# leo_MCU.net
KiCad netlist of a schematic drawn in Altium Designer
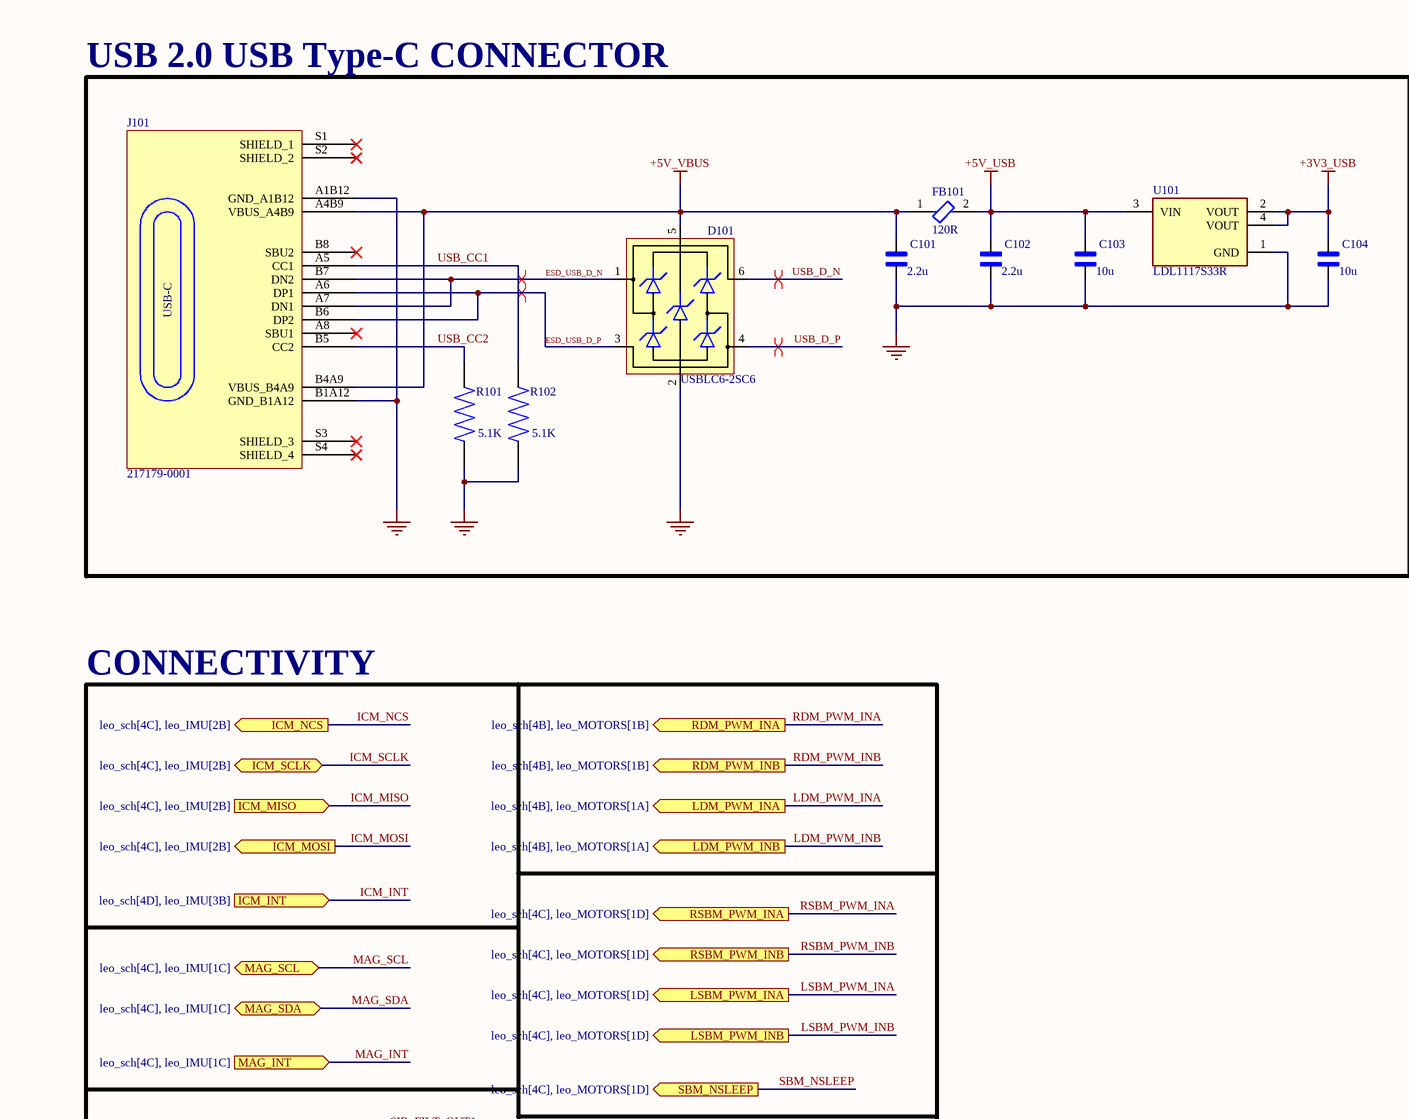
[diagram p0: leo_MCU.SchDoc, top left]
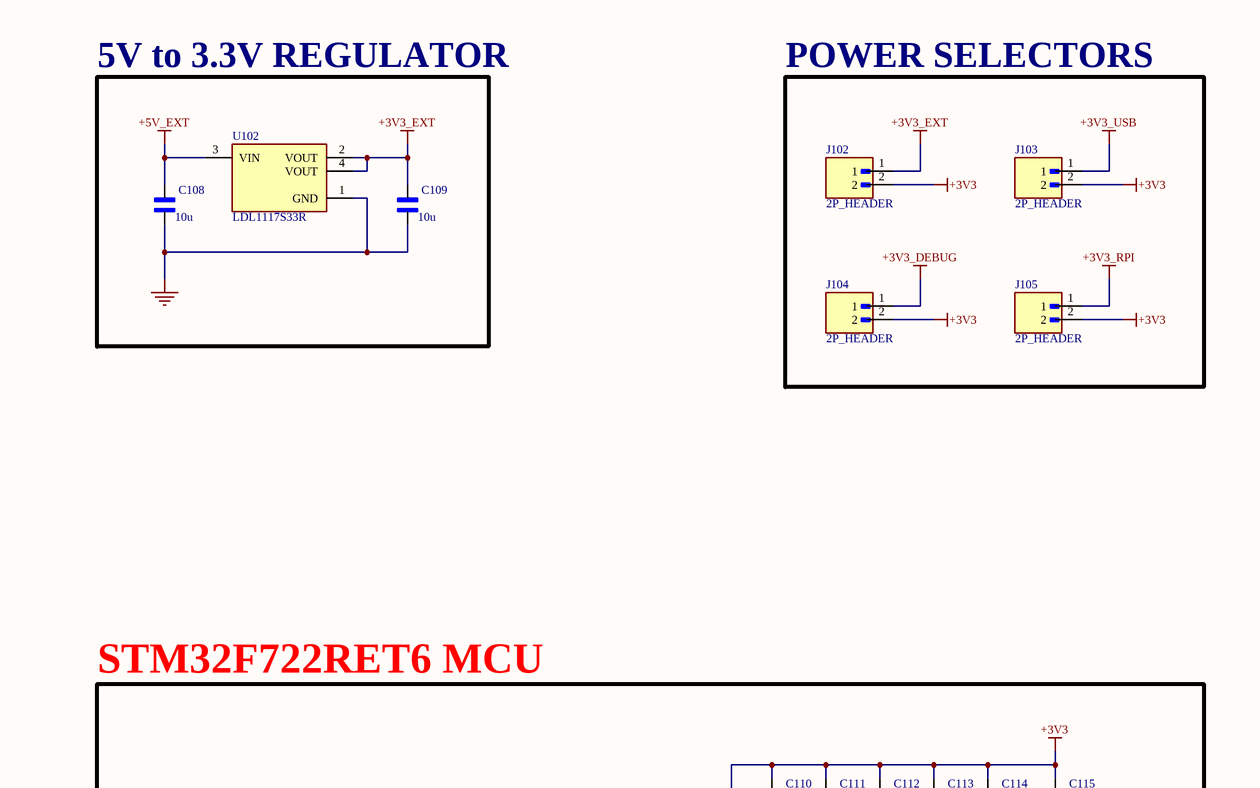
[diagram p1: leo_MCU.SchDoc, top right]
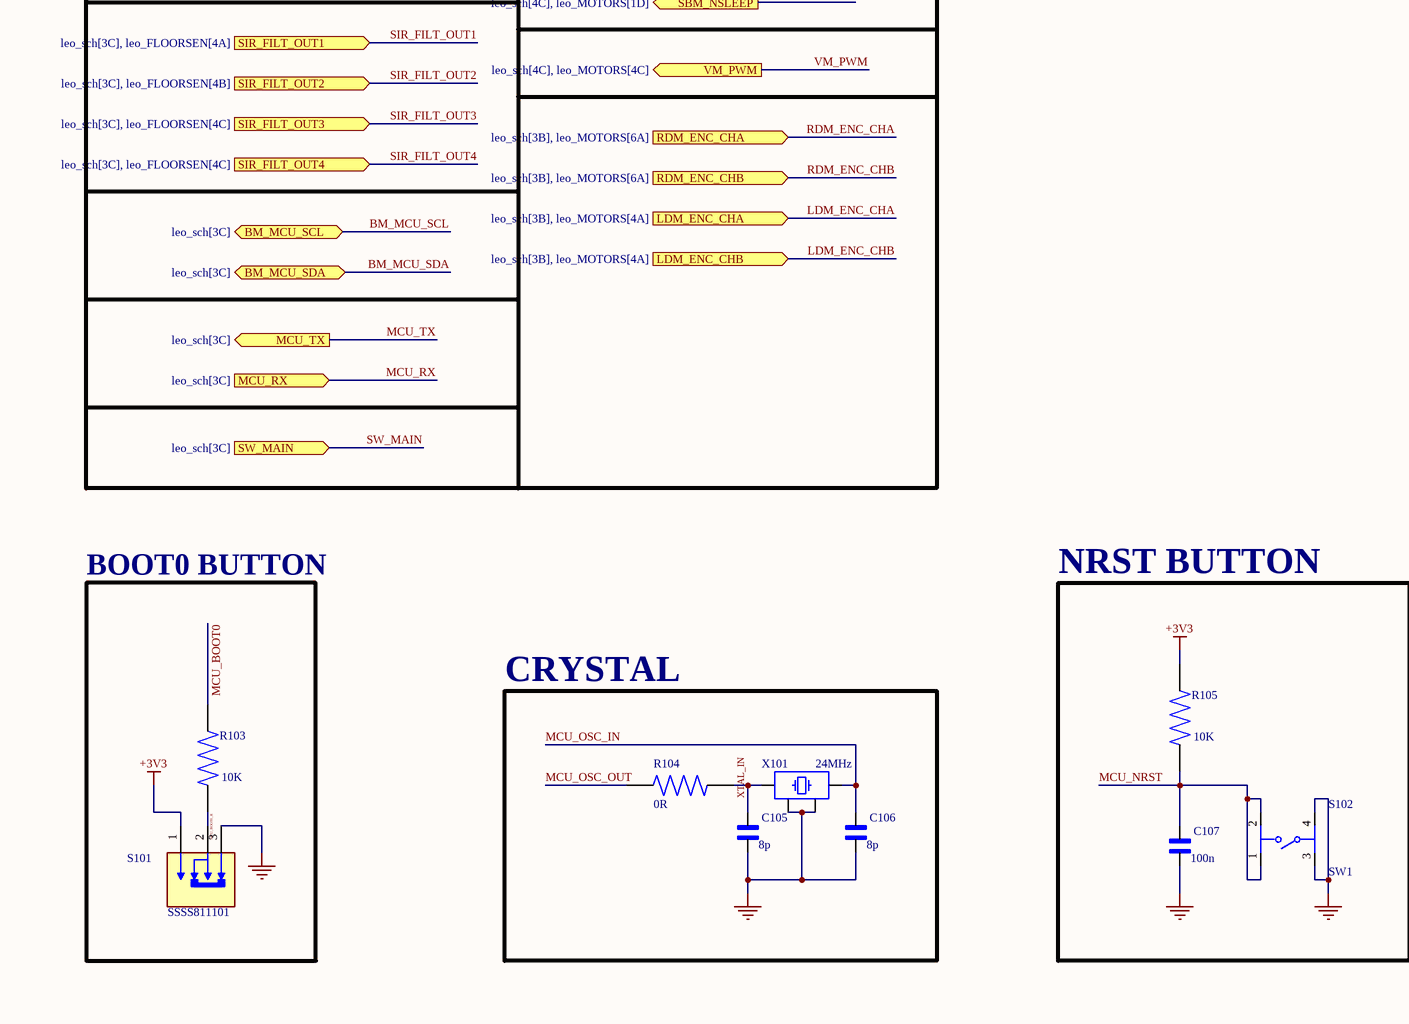
[diagram p2: leo_MCU.SchDoc, bottom left]
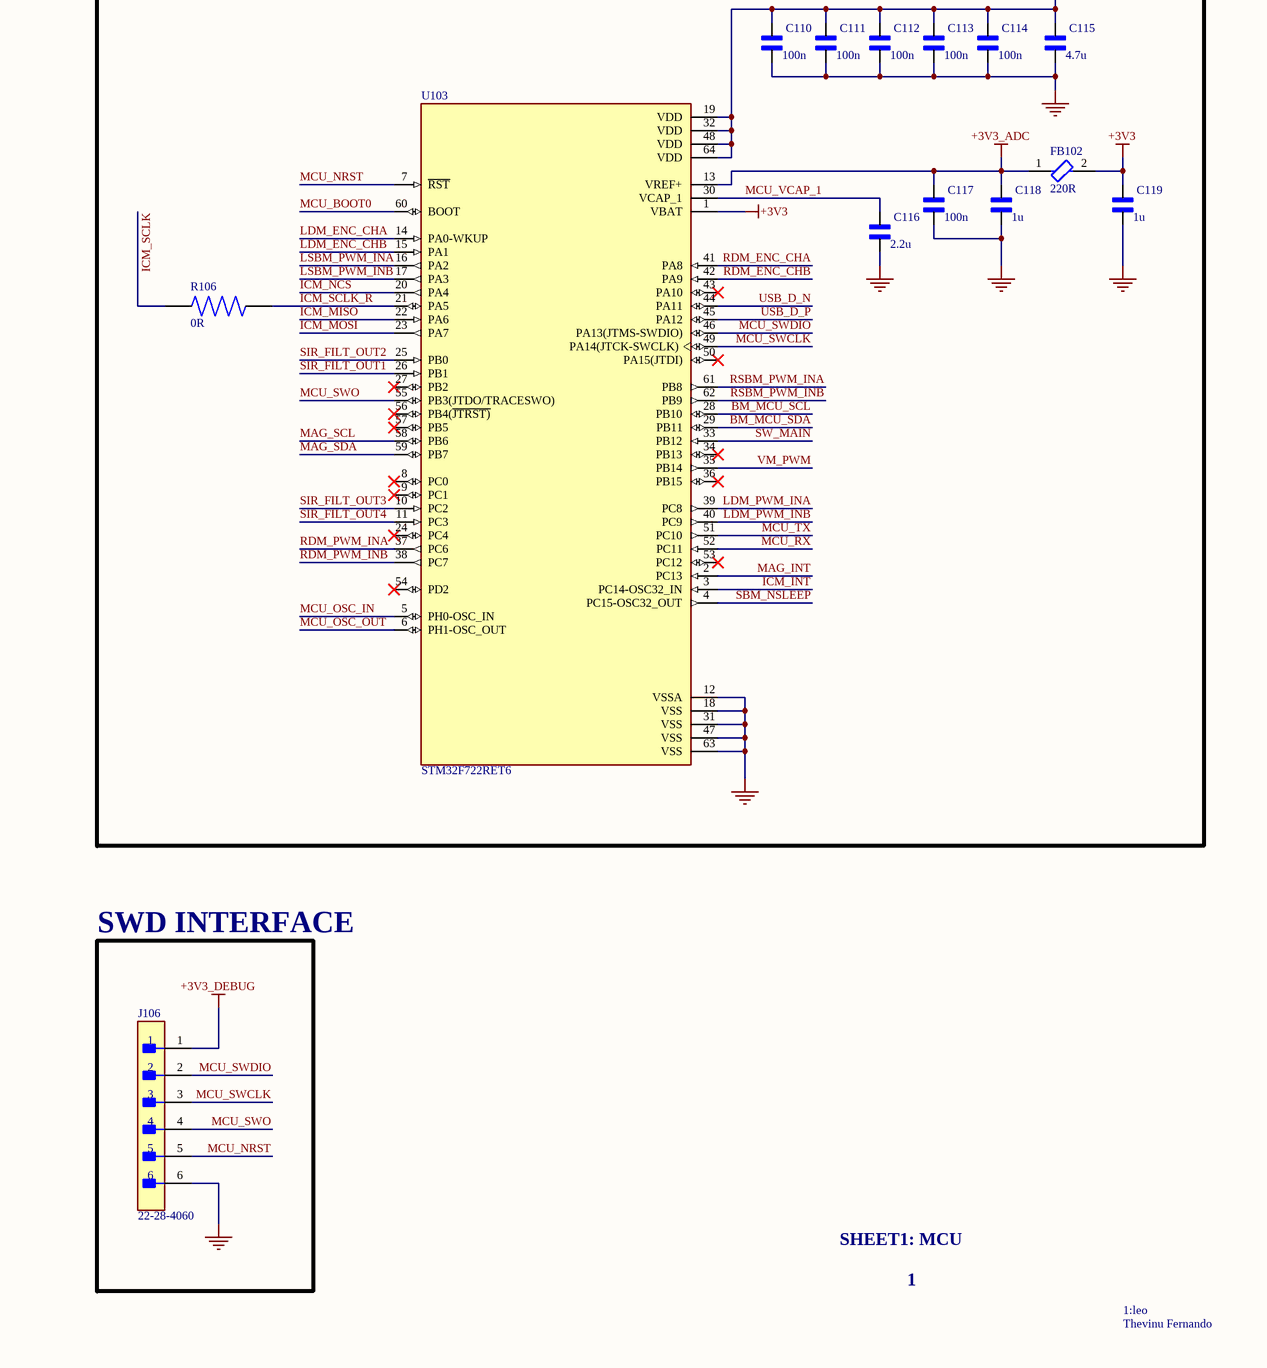
[diagram p3: leo_MCU.SchDoc, bottom right]

(export (version "E")
  (design (tool "Eeschema 10.0.6"))
  (components
    (comp (ref "C101")
      (value "2.2u")
      (footprint "CAP_0603")
      (description "Ceramic Capacitor X5R 0603 (1608 Metric)")
      (fields (field (name "MF") "Samsung Electro-Mechanics") (field (name "MP") "CL10A475KO8NNNC"))
      (libsource (lib "leo_schlib") (part "CAP_0603"))
    )
    (comp (ref "C102")
      (value "2.2u")
      (footprint "CAP_0603")
      (description "Ceramic Capacitor X5R 0603 (1608 Metric)")
      (fields (field (name "MF") "Samsung Electro-Mechanics") (field (name "MP") "CL10A475KO8NNNC"))
      (libsource (lib "leo_schlib") (part "CAP_0603"))
    )
    (comp (ref "C103")
      (value "10u")
      (footprint "CAP_0805")
      (description "Ceramic Capacitor X7R 0805 (2012 Metric)")
      (fields (field (name "MF") "Samsung Electro-Mechanics") (field (name "MP") "CL21B106KOQNNNE"))
      (libsource (lib "leo_schlib") (part "CAP_0805"))
    )
    (comp (ref "C104")
      (value "10u")
      (footprint "CAP_0805")
      (description "Ceramic Capacitor X7R 0805 (2012 Metric)")
      (fields (field (name "MF") "Samsung Electro-Mechanics") (field (name "MP") "CL21B106KOQNNNE"))
      (libsource (lib "leo_schlib") (part "CAP_0805"))
    )
    (comp (ref "C105")
      (value "8p")
      (footprint "CAP_0402")
      (description "Ceramic Capacitor X7R 0402 (1005 Metric)")
      (fields (field (name "MF") "Samsung") (field (name "MP") "CL05B104KO5NNNC"))
      (libsource (lib "leo_schlib") (part "CAP_0402"))
    )
    (comp (ref "C106")
      (value "8p")
      (footprint "CAP_0402")
      (description "Ceramic Capacitor X7R 0402 (1005 Metric)")
      (fields (field (name "MF") "Samsung") (field (name "MP") "CL05B104KO5NNNC"))
      (libsource (lib "leo_schlib") (part "CAP_0402"))
    )
    (comp (ref "C107")
      (value "100n")
      (footprint "CAP_0402")
      (description "Ceramic Capacitor X7R 0402 (1005 Metric)")
      (fields (field (name "MF") "Samsung") (field (name "MP") "CL05B104KO5NNNC"))
      (libsource (lib "leo_schlib") (part "CAP_0402"))
    )
    (comp (ref "C108")
      (value "10u")
      (footprint "CAP_0805")
      (description "Ceramic Capacitor X7R 0805 (2012 Metric)")
      (fields (field (name "MF") "Samsung Electro-Mechanics") (field (name "MP") "CL21B106KOQNNNE"))
      (libsource (lib "leo_schlib") (part "CAP_0805"))
    )
    (comp (ref "C109")
      (value "10u")
      (footprint "CAP_0805")
      (description "Ceramic Capacitor X7R 0805 (2012 Metric)")
      (fields (field (name "MF") "Samsung Electro-Mechanics") (field (name "MP") "CL21B106KOQNNNE"))
      (libsource (lib "leo_schlib") (part "CAP_0805"))
    )
    (comp (ref "C110")
      (value "100n")
      (footprint "CAP_0402")
      (description "Ceramic Capacitor X7R 0402 (1005 Metric)")
      (fields (field (name "MF") "Samsung") (field (name "MP") "CL05B104KO5NNNC"))
      (libsource (lib "leo_schlib") (part "CAP_0402"))
    )
    (comp (ref "C111")
      (value "100n")
      (footprint "CAP_0402")
      (description "Ceramic Capacitor X7R 0402 (1005 Metric)")
      (fields (field (name "MF") "Samsung") (field (name "MP") "CL05B104KO5NNNC"))
      (libsource (lib "leo_schlib") (part "CAP_0402"))
    )
    (comp (ref "C112")
      (value "100n")
      (footprint "CAP_0402")
      (description "Ceramic Capacitor X7R 0402 (1005 Metric)")
      (fields (field (name "MF") "Samsung") (field (name "MP") "CL05B104KO5NNNC"))
      (libsource (lib "leo_schlib") (part "CAP_0402"))
    )
    (comp (ref "C113")
      (value "100n")
      (footprint "CAP_0402")
      (description "Ceramic Capacitor X7R 0402 (1005 Metric)")
      (fields (field (name "MF") "Samsung") (field (name "MP") "CL05B104KO5NNNC"))
      (libsource (lib "leo_schlib") (part "CAP_0402"))
    )
    (comp (ref "C114")
      (value "100n")
      (footprint "CAP_0402")
      (description "Ceramic Capacitor X7R 0402 (1005 Metric)")
      (fields (field (name "MF") "Samsung") (field (name "MP") "CL05B104KO5NNNC"))
      (libsource (lib "leo_schlib") (part "CAP_0402"))
    )
    (comp (ref "C115")
      (value "4.7u")
      (footprint "CAP_0603")
      (description "Ceramic Capacitor X5R 0603 (1608 Metric)")
      (fields (field (name "MF") "Samsung Electro-Mechanics") (field (name "MP") "CL10A475KO8NNNC"))
      (libsource (lib "leo_schlib") (part "CAP_0603"))
    )
    (comp (ref "C116")
      (value "2.2u")
      (footprint "CAP_0603")
      (description "Ceramic Capacitor X5R 0603 (1608 Metric)")
      (fields (field (name "MF") "Samsung Electro-Mechanics") (field (name "MP") "CL10A475KO8NNNC"))
      (libsource (lib "leo_schlib") (part "CAP_0603"))
    )
    (comp (ref "C117")
      (value "100n")
      (footprint "CAP_0402")
      (description "Ceramic Capacitor X7R 0402 (1005 Metric)")
      (fields (field (name "MF") "Samsung") (field (name "MP") "CL05B104KO5NNNC"))
      (libsource (lib "leo_schlib") (part "CAP_0402"))
    )
    (comp (ref "C118")
      (value "1u")
      (footprint "CAP_0603")
      (description "Ceramic Capacitor X5R 0603 (1608 Metric)")
      (fields (field (name "MF") "Samsung Electro-Mechanics") (field (name "MP") "CL10A475KO8NNNC"))
      (libsource (lib "leo_schlib") (part "CAP_0603"))
    )
    (comp (ref "C119")
      (value "1u")
      (footprint "CAP_0603")
      (description "Ceramic Capacitor X5R 0603 (1608 Metric)")
      (fields (field (name "MF") "Samsung Electro-Mechanics") (field (name "MP") "CL10A475KO8NNNC"))
      (libsource (lib "leo_schlib") (part "CAP_0603"))
    )
    (comp (ref "D101")
      (value "USBLC6-2SC6")
      (footprint "SOT95P280X145-6N")
      (description "Low-Capacitance ESD Protection USB")
      (fields (field (name "MANUFACTURER") "STMicroelectronics"))
      (libsource (lib "leo_schlib") (part "USBLC6-2SC6"))
    )
    (comp (ref "FB101")
      (value "120R")
      (footprint "FP-MPZ1608-0_8-IPC_B")
      (description "120Ω@100MHz 1 Line Ferrite Bead 0603 3A 30mΩ")
      (fields (field (name "TOLERANCE") "25%"))
      (libsource (lib "leo_schlib") (part "Ferrite_Bead_120R_0603"))
    )
    (comp (ref "FB102")
      (value "220R")
      (footprint "FP-MPZ1608-0_8-IPC_B")
      (description "Power line Ferrite Bead 220Ω @ 100MHz 2.2A DCR 0.05Ω SMD 0603")
      (fields (field (name "TOLERANCE") "25%"))
      (libsource (lib "leo_schlib") (part "Ferrite_Bead_0603"))
    )
    (comp (ref "J101")
      (value "217179-0001")
      (footprint "FP-2171790001-MFG USB-C 2.0")
      (description "USB 2.0 5A 1 16P -40℃~+85℃ SMD USB, DVI, HDMI Connector Assemblies RoHS")
      (fields (field (name "MANUFACTURER") "Molex") (field (name "LCSC PART NUMBER") "C3197684"))
      (libsource (lib "leo_schlib") (part "USB_Connector"))
    )
    (comp (ref "J102")
      (value "2P_HEADER")
      (footprint "HARWIN_M20-9990246 2P Header")
      (description "2.54mm (0.1) Pitch SIL Vertical Throughboard Pin Header, 6.1mm mating pin height, tin, 2 contacts")
      (fields (field (name "MF") "Harwin") (field (name "MP") "M20-9990246"))
      (libsource (lib "leo_schlib") (part "2P_HEADER"))
    )
    (comp (ref "J103")
      (value "2P_HEADER")
      (footprint "HARWIN_M20-9990246 2P Header")
      (description "2.54mm (0.1) Pitch SIL Vertical Throughboard Pin Header, 6.1mm mating pin height, tin, 2 contacts")
      (fields (field (name "MF") "Harwin") (field (name "MP") "M20-9990246"))
      (libsource (lib "leo_schlib") (part "2P_HEADER"))
    )
    (comp (ref "J104")
      (value "2P_HEADER")
      (footprint "HARWIN_M20-9990246 2P Header")
      (description "2.54mm (0.1) Pitch SIL Vertical Throughboard Pin Header, 6.1mm mating pin height, tin, 2 contacts")
      (fields (field (name "MF") "Harwin") (field (name "MP") "M20-9990246"))
      (libsource (lib "leo_schlib") (part "2P_HEADER"))
    )
    (comp (ref "J105")
      (value "2P_HEADER")
      (footprint "HARWIN_M20-9990246 2P Header")
      (description "2.54mm (0.1) Pitch SIL Vertical Throughboard Pin Header, 6.1mm mating pin height, tin, 2 contacts")
      (fields (field (name "MF") "Harwin") (field (name "MP") "M20-9990246"))
      (libsource (lib "leo_schlib") (part "2P_HEADER"))
    )
    (comp (ref "J106")
      (value "22-28-4060")
      (footprint "FP-22-28-4060-MFG")
      (description "CONN HEADER VERT 6POS 2.54MM")
      (libsource (lib "leo_schlib") (part "6P_M_HEADER"))
    )
    (comp (ref "R101")
      (value "5.1K")
      (footprint "RES_0402")
      (description "Chip Resistor 0402 (1005 Metric) Automotive AEC-Q200 Thick Film")
      (fields (field (name "MF") "Panasonic") (field (name "MP") "ERJ-2RKF1002X"))
      (libsource (lib "leo_schlib") (part "RES_0402"))
    )
    (comp (ref "R102")
      (value "5.1K")
      (footprint "RES_0402")
      (description "Chip Resistor 0402 (1005 Metric) Automotive AEC-Q200 Thick Film")
      (fields (field (name "MF") "Panasonic") (field (name "MP") "ERJ-2RKF1002X"))
      (libsource (lib "leo_schlib") (part "RES_0402"))
    )
    (comp (ref "R103")
      (value "10K")
      (footprint "RES_0402")
      (description "Chip Resistor 0402 (1005 Metric) Automotive AEC-Q200 Thick Film")
      (fields (field (name "MF") "Panasonic") (field (name "MP") "ERJ-2RKF1002X"))
      (libsource (lib "leo_schlib") (part "RES_0402"))
    )
    (comp (ref "R104")
      (value "0R")
      (footprint "RES_0402")
      (description "Chip Resistor 0402 (1005 Metric) Automotive AEC-Q200 Thick Film")
      (fields (field (name "MF") "Panasonic") (field (name "MP") "ERJ-2RKF1002X"))
      (libsource (lib "leo_schlib") (part "RES_0402"))
    )
    (comp (ref "R105")
      (value "10K")
      (footprint "RES_0402")
      (description "Chip Resistor 0402 (1005 Metric) Automotive AEC-Q200 Thick Film")
      (fields (field (name "MF") "Panasonic") (field (name "MP") "ERJ-2RKF1002X"))
      (libsource (lib "leo_schlib") (part "RES_0402"))
    )
    (comp (ref "R106")
      (value "0R")
      (footprint "RES_0402")
      (description "Chip Resistor 0402 (1005 Metric) Automotive AEC-Q200 Thick Film")
      (fields (field (name "MF") "Panasonic") (field (name "MP") "ERJ-2RKF1002X"))
      (libsource (lib "leo_schlib") (part "RES_0402"))
    )
    (comp (ref "S101")
      (value "SSSS811101")
      (footprint "SW_SSSS811101")
      (description "Switch Slide SP Side Slide 0.3A 5VDC 10000Cycles Gull Wing SMD T/R")
      (fields (field (name "MF") "ALPS"))
      (libsource (lib "leo_schlib") (part "SSSS811101"))
    )
    (comp (ref "S102")
      (value "SW1")
      (footprint "FP-PTS645SM43SMTR92LFS-MFG")
      (description "Tactile Switch SPST 160gf 4.3mm Gull Wing 6mm x 6mm Surface Mount")
      (libsource (lib "leo_schlib") (part "PTS645SM43SMTR92LFS"))
    )
    (comp (ref "U101")
      (value "LDL1117S33R")
      (footprint "FP-SOT223-0046067-IPC_A")
      (description "IC REG LINEAR 3.3V 1.2A SOT223")
      (fields
        (field (name "OCTOPART") "https://octopart.com/ldl1117s33r-stmicroelectronics-81876163")
        (field (name "MANUFACTURER") "STMicroelectronics")
      )
      (libsource (lib "leo_schlib") (part "LDO_LDL1117S33R"))
    )
    (comp (ref "U102")
      (value "LDL1117S33R")
      (footprint "FP-SOT223-0046067-IPC_A")
      (description "IC REG LINEAR 3.3V 1.2A SOT223")
      (fields
        (field (name "OCTOPART") "https://octopart.com/ldl1117s33r-stmicroelectronics-81876163")
        (field (name "MANUFACTURER") "STMicroelectronics")
      )
      (libsource (lib "leo_schlib") (part "LDO_LDL1117S33R"))
    )
    (comp (ref "U103")
      (value "STM32F722RET6")
      (footprint "FP-LQFP64-5W-IPC_B")
      (description "ARM Cortex-M7 32 Bit 216MHz 50 LQFP-64(10x10) Microcontrollers RoHS")
      (fields (field (name "MF") "STMicroelectronics"))
      (libsource (lib "leo_schlib") (part "STM32F722RET6"))
    )
    (comp (ref "X101")
      (value "24MHz")
      (footprint "XTAL_3225")
      (description "Crystal SMD 24MHz 10PPM 7pF 3225")
      (fields
        (field (name "MANUFACTURER") "Epson")
        (field (name "MANUFACTURER PART NUMBER") "TSX-3225 24.0000MF15X-AC")
      )
      (libsource (lib "leo_schlib") (part "TSX-3225_24.0000MF15X-AC"))
    )
  )
  (nets
    (net (code "1") (name "+3V3") (class "Default")
      (node (ref "C110") (pin "2") (pinfunction "2_2") (pintype "passive"))
      (node (ref "C111") (pin "2") (pinfunction "2_2") (pintype "passive"))
      (node (ref "C112") (pin "2") (pinfunction "2_2") (pintype "passive"))
      (node (ref "C113") (pin "2") (pinfunction "2_2") (pintype "passive"))
      (node (ref "C114") (pin "2") (pinfunction "2_2") (pintype "passive"))
      (node (ref "C115") (pin "2") (pinfunction "2_2") (pintype "passive"))
      (node (ref "C119") (pin "2") (pinfunction "2_2") (pintype "passive"))
      (node (ref "FB102") (pin "2") (pinfunction "2_2") (pintype "passive"))
      (node (ref "J102") (pin "2") (pinfunction "2_2") (pintype "passive"))
      (node (ref "J103") (pin "2") (pinfunction "2_2") (pintype "passive"))
      (node (ref "J104") (pin "2") (pinfunction "2_2") (pintype "passive"))
      (node (ref "J105") (pin "2") (pinfunction "2_2") (pintype "passive"))
      (node (ref "R105") (pin "2") (pinfunction "2_2") (pintype "passive"))
      (node (ref "S101") (pin "1") (pinfunction "1_1") (pintype "passive"))
      (node (ref "U103") (pin "1") (pinfunction "VBAT_1") (pintype "power_in"))
      (node (ref "U103") (pin "19") (pinfunction "VDD_19") (pintype "power_in"))
      (node (ref "U103") (pin "32") (pinfunction "VDD_32") (pintype "power_in"))
      (node (ref "U103") (pin "48") (pinfunction "VDD_48") (pintype "power_in"))
      (node (ref "U103") (pin "64") (pinfunction "VDD_64") (pintype "power_in"))
    )
    (net (code "2") (name "+3V3_ADC") (class "Default")
      (node (ref "C117") (pin "2") (pinfunction "2_2") (pintype "passive"))
      (node (ref "C118") (pin "2") (pinfunction "2_2") (pintype "passive"))
      (node (ref "FB102") (pin "1") (pinfunction "1_1") (pintype "passive"))
      (node (ref "U103") (pin "13") (pinfunction "VREF+_13") (pintype "power_in"))
    )
    (net (code "3") (name "+3V3_DEBUG") (class "Default")
      (node (ref "J104") (pin "1") (pinfunction "1_1") (pintype "passive"))
      (node (ref "J106") (pin "1") (pinfunction "1_1") (pintype "passive"))
    )
    (net (code "4") (name "+3V3_EXT") (class "Default")
      (node (ref "C109") (pin "1") (pinfunction "1_1") (pintype "passive"))
      (node (ref "J102") (pin "1") (pinfunction "1_1") (pintype "passive"))
      (node (ref "U102") (pin "2") (pinfunction "VOUT_2") (pintype "power_in"))
      (node (ref "U102") (pin "4") (pinfunction "VOUT_4") (pintype "power_in"))
    )
    (net (code "5") (name "+3V3_RPI") (class "Default")
      (node (ref "J105") (pin "1") (pinfunction "1_1") (pintype "passive"))
    )
    (net (code "6") (name "+3V3_USB") (class "Default")
      (node (ref "C104") (pin "1") (pinfunction "1_1") (pintype "passive"))
      (node (ref "J103") (pin "1") (pinfunction "1_1") (pintype "passive"))
      (node (ref "U101") (pin "2") (pinfunction "VOUT_2") (pintype "power_in"))
      (node (ref "U101") (pin "4") (pinfunction "VOUT_4") (pintype "power_in"))
    )
    (net (code "7") (name "+5V_EXT") (class "Default")
      (node (ref "C108") (pin "1") (pinfunction "1_1") (pintype "passive"))
      (node (ref "U102") (pin "3") (pinfunction "VIN_3") (pintype "power_in"))
    )
    (net (code "8") (name "+5V_USB") (class "Default")
      (node (ref "C102") (pin "2") (pinfunction "2_2") (pintype "passive"))
      (node (ref "C103") (pin "1") (pinfunction "1_1") (pintype "passive"))
      (node (ref "FB101") (pin "2") (pinfunction "2_2") (pintype "passive"))
      (node (ref "U101") (pin "3") (pinfunction "VIN_3") (pintype "power_in"))
    )
    (net (code "9") (name "+5V_VBUS") (class "Default")
      (node (ref "C101") (pin "2") (pinfunction "2_2") (pintype "passive"))
      (node (ref "D101") (pin "5") (pinfunction "VBUS_5") (pintype "power_in"))
      (node (ref "FB101") (pin "1") (pinfunction "1_1") (pintype "passive"))
      (node (ref "J101") (pin "A4B9") (pinfunction "VBUS_A4B9_A4B9") (pintype "passive"))
      (node (ref "J101") (pin "B4A9") (pinfunction "VBUS_B4A9_B4A9") (pintype "passive"))
    )
    (net (code "10") (name "/BM_MCU_SCL") (class "Default")
      (node (ref "U103") (pin "28") (pinfunction "PB10_28") (pintype "bidirectional"))
    )
    (net (code "11") (name "/BM_MCU_SDA") (class "Default")
      (node (ref "U103") (pin "29") (pinfunction "PB11_29") (pintype "bidirectional"))
    )
    (net (code "12") (name "/ESD_USB_D_N") (class "Default")
      (node (ref "D101") (pin "1") (pinfunction "IO1_1") (pintype "bidirectional"))
      (node (ref "J101") (pin "A7") (pinfunction "DN1_A7") (pintype "passive"))
      (node (ref "J101") (pin "B7") (pinfunction "DN2_B7") (pintype "passive"))
    )
    (net (code "13") (name "/ESD_USB_D_P") (class "Default")
      (node (ref "D101") (pin "3") (pinfunction "IO2_3") (pintype "bidirectional"))
      (node (ref "J101") (pin "A6") (pinfunction "DP1_A6") (pintype "passive"))
      (node (ref "J101") (pin "B6") (pinfunction "DP2_B6") (pintype "passive"))
    )
    (net (code "14") (name "/ICM_INT") (class "Default")
      (node (ref "U103") (pin "3") (pinfunction "PC14-OSC32_IN_3") (pintype "input"))
    )
    (net (code "15") (name "/ICM_MISO") (class "Default")
      (node (ref "U103") (pin "22") (pinfunction "PA6_22") (pintype "input"))
    )
    (net (code "16") (name "/ICM_MOSI") (class "Default")
      (node (ref "U103") (pin "23") (pinfunction "PA7_23") (pintype "output"))
    )
    (net (code "17") (name "/ICM_NCS") (class "Default")
      (node (ref "U103") (pin "20") (pinfunction "PA4_20") (pintype "output"))
    )
    (net (code "18") (name "/ICM_SCLK") (class "Default")
      (node (ref "R106") (pin "2") (pinfunction "2_2") (pintype "passive"))
    )
    (net (code "19") (name "/ICM_SCLK_R") (class "Default")
      (node (ref "R106") (pin "1") (pinfunction "1_1") (pintype "passive"))
      (node (ref "U103") (pin "21") (pinfunction "PA5_21") (pintype "bidirectional"))
    )
    (net (code "20") (name "/LDM_ENC_CHA") (class "Default")
      (node (ref "U103") (pin "14") (pinfunction "PA0-WKUP_14") (pintype "input"))
    )
    (net (code "21") (name "/LDM_ENC_CHB") (class "Default")
      (node (ref "U103") (pin "15") (pinfunction "PA1_15") (pintype "input"))
    )
    (net (code "22") (name "/LDM_PWM_INA") (class "Default")
      (node (ref "U103") (pin "39") (pinfunction "PC8_39") (pintype "output"))
    )
    (net (code "23") (name "/LDM_PWM_INB") (class "Default")
      (node (ref "U103") (pin "40") (pinfunction "PC9_40") (pintype "output"))
    )
    (net (code "24") (name "/LSBM_PWM_INA") (class "Default")
      (node (ref "U103") (pin "16") (pinfunction "PA2_16") (pintype "output"))
    )
    (net (code "25") (name "/LSBM_PWM_INB") (class "Default")
      (node (ref "U103") (pin "17") (pinfunction "PA3_17") (pintype "output"))
    )
    (net (code "26") (name "/MAG_INT") (class "Default")
      (node (ref "U103") (pin "2") (pinfunction "PC13_2") (pintype "input"))
    )
    (net (code "27") (name "/MAG_SCL") (class "Default")
      (node (ref "U103") (pin "58") (pinfunction "PB6_58") (pintype "bidirectional"))
    )
    (net (code "28") (name "/MAG_SDA") (class "Default")
      (node (ref "U103") (pin "59") (pinfunction "PB7_59") (pintype "bidirectional"))
    )
    (net (code "29") (name "/MCU_BOOT0") (class "Default")
      (node (ref "R103") (pin "2") (pinfunction "2_2") (pintype "passive"))
      (node (ref "U103") (pin "60") (pinfunction "BOOT_60") (pintype "bidirectional"))
    )
    (net (code "30") (name "/MCU_BOOT0_R") (class "Default")
      (node (ref "R103") (pin "1") (pinfunction "1_1") (pintype "passive"))
      (node (ref "S101") (pin "2") (pinfunction "2_2") (pintype "passive"))
    )
    (net (code "31") (name "/MCU_NRST") (class "Default")
      (node (ref "C107") (pin "2") (pinfunction "2_2") (pintype "passive"))
      (node (ref "J106") (pin "5") (pinfunction "5_5") (pintype "passive"))
      (node (ref "R105") (pin "1") (pinfunction "1_1") (pintype "passive"))
      (node (ref "S102") (pin "1") (pinfunction "1_1") (pintype "passive"))
      (node (ref "S102") (pin "2") (pinfunction "2_2") (pintype "passive"))
      (node (ref "U103") (pin "7") (pinfunction "~{RST}_7") (pintype "input"))
    )
    (net (code "32") (name "/MCU_OSC_IN") (class "Default")
      (node (ref "C106") (pin "2") (pinfunction "2_2") (pintype "passive"))
      (node (ref "U103") (pin "5") (pinfunction "PH0-OSC_IN_5") (pintype "bidirectional"))
      (node (ref "X101") (pin "3") (pinfunction "3_3") (pintype "passive"))
    )
    (net (code "33") (name "/MCU_OSC_OUT") (class "Default")
      (node (ref "R104") (pin "2") (pinfunction "2_2") (pintype "passive"))
      (node (ref "U103") (pin "6") (pinfunction "PH1-OSC_OUT_6") (pintype "bidirectional"))
    )
    (net (code "34") (name "/MCU_RX") (class "Default")
      (node (ref "U103") (pin "52") (pinfunction "PC11_52") (pintype "input"))
    )
    (net (code "35") (name "/MCU_SWCLK") (class "Default")
      (node (ref "J106") (pin "3") (pinfunction "3_3") (pintype "passive"))
      (node (ref "U103") (pin "49") (pinfunction "PA14(JTCK-SWCLK)_49") (pintype "bidirectional"))
    )
    (net (code "36") (name "/MCU_SWDIO") (class "Default")
      (node (ref "J106") (pin "2") (pinfunction "2_2") (pintype "passive"))
      (node (ref "U103") (pin "46") (pinfunction "PA13(JTMS-SWDIO)_46") (pintype "bidirectional"))
    )
    (net (code "37") (name "/MCU_SWO") (class "Default")
      (node (ref "J106") (pin "4") (pinfunction "4_4") (pintype "passive"))
      (node (ref "U103") (pin "55") (pinfunction "PB3(JTDO/TRACESWO)_55") (pintype "bidirectional"))
    )
    (net (code "38") (name "/MCU_TX") (class "Default")
      (node (ref "U103") (pin "51") (pinfunction "PC10_51") (pintype "output"))
    )
    (net (code "39") (name "/MCU_VCAP_1") (class "Default")
      (node (ref "C116") (pin "2") (pinfunction "2_2") (pintype "passive"))
      (node (ref "U103") (pin "30") (pinfunction "VCAP_1_30") (pintype "power_in"))
    )
    (net (code "40") (name "/RDM_ENC_CHA") (class "Default")
      (node (ref "U103") (pin "41") (pinfunction "PA8_41") (pintype "input"))
    )
    (net (code "41") (name "/RDM_ENC_CHB") (class "Default")
      (node (ref "U103") (pin "42") (pinfunction "PA9_42") (pintype "input"))
    )
    (net (code "42") (name "/RDM_PWM_INA") (class "Default")
      (node (ref "U103") (pin "37") (pinfunction "PC6_37") (pintype "output"))
    )
    (net (code "43") (name "/RDM_PWM_INB") (class "Default")
      (node (ref "U103") (pin "38") (pinfunction "PC7_38") (pintype "output"))
    )
    (net (code "44") (name "/RSBM_PWM_INA") (class "Default")
      (node (ref "U103") (pin "61") (pinfunction "PB8_61") (pintype "output"))
    )
    (net (code "45") (name "/RSBM_PWM_INB") (class "Default")
      (node (ref "U103") (pin "62") (pinfunction "PB9_62") (pintype "output"))
    )
    (net (code "46") (name "/SBM_NSLEEP") (class "Default")
      (node (ref "U103") (pin "4") (pinfunction "PC15-OSC32_OUT_4") (pintype "output"))
    )
    (net (code "47") (name "/SIR_FILT_OUT1") (class "Default")
      (node (ref "U103") (pin "26") (pinfunction "PB1_26") (pintype "input"))
    )
    (net (code "48") (name "/SIR_FILT_OUT2") (class "Default")
      (node (ref "U103") (pin "25") (pinfunction "PB0_25") (pintype "input"))
    )
    (net (code "49") (name "/SIR_FILT_OUT3") (class "Default")
      (node (ref "U103") (pin "10") (pinfunction "PC2_10") (pintype "input"))
    )
    (net (code "50") (name "/SIR_FILT_OUT4") (class "Default")
      (node (ref "U103") (pin "11") (pinfunction "PC3_11") (pintype "input"))
    )
    (net (code "51") (name "/SW_MAIN") (class "Default")
      (node (ref "U103") (pin "33") (pinfunction "PB12_33") (pintype "input"))
    )
    (net (code "52") (name "/USB_CC1") (class "Default")
      (node (ref "J101") (pin "A5") (pinfunction "CC1_A5") (pintype "passive"))
      (node (ref "R102") (pin "1") (pinfunction "1_1") (pintype "passive"))
    )
    (net (code "53") (name "/USB_CC2") (class "Default")
      (node (ref "J101") (pin "B5") (pinfunction "CC2_B5") (pintype "passive"))
      (node (ref "R101") (pin "1") (pinfunction "1_1") (pintype "passive"))
    )
    (net (code "54") (name "/USB_D_N") (class "Default")
      (node (ref "D101") (pin "6") (pinfunction "IO1_6") (pintype "bidirectional"))
      (node (ref "U103") (pin "44") (pinfunction "PA11_44") (pintype "bidirectional"))
    )
    (net (code "55") (name "/USB_D_P") (class "Default")
      (node (ref "D101") (pin "4") (pinfunction "IO2_4") (pintype "bidirectional"))
      (node (ref "U103") (pin "45") (pinfunction "PA12_45") (pintype "bidirectional"))
    )
    (net (code "56") (name "/VM_PWM") (class "Default")
      (node (ref "U103") (pin "35") (pinfunction "PB14_35") (pintype "output"))
    )
    (net (code "57") (name "/XTAL_IN") (class "Default")
      (node (ref "C105") (pin "2") (pinfunction "2_2") (pintype "passive"))
      (node (ref "R104") (pin "1") (pinfunction "1_1") (pintype "passive"))
      (node (ref "X101") (pin "1") (pinfunction "1_1") (pintype "passive"))
    )
    (net (code "58") (name "GND") (class "Default")
      (node (ref "C101") (pin "1") (pinfunction "1_1") (pintype "passive"))
      (node (ref "C102") (pin "1") (pinfunction "1_1") (pintype "passive"))
      (node (ref "C103") (pin "2") (pinfunction "2_2") (pintype "passive"))
      (node (ref "C104") (pin "2") (pinfunction "2_2") (pintype "passive"))
      (node (ref "C105") (pin "1") (pinfunction "1_1") (pintype "passive"))
      (node (ref "C106") (pin "1") (pinfunction "1_1") (pintype "passive"))
      (node (ref "C107") (pin "1") (pinfunction "1_1") (pintype "passive"))
      (node (ref "C108") (pin "2") (pinfunction "2_2") (pintype "passive"))
      (node (ref "C109") (pin "2") (pinfunction "2_2") (pintype "passive"))
      (node (ref "C110") (pin "1") (pinfunction "1_1") (pintype "passive"))
      (node (ref "C111") (pin "1") (pinfunction "1_1") (pintype "passive"))
      (node (ref "C112") (pin "1") (pinfunction "1_1") (pintype "passive"))
      (node (ref "C113") (pin "1") (pinfunction "1_1") (pintype "passive"))
      (node (ref "C114") (pin "1") (pinfunction "1_1") (pintype "passive"))
      (node (ref "C115") (pin "1") (pinfunction "1_1") (pintype "passive"))
      (node (ref "C116") (pin "1") (pinfunction "1_1") (pintype "passive"))
      (node (ref "C117") (pin "1") (pinfunction "1_1") (pintype "passive"))
      (node (ref "C118") (pin "1") (pinfunction "1_1") (pintype "passive"))
      (node (ref "C119") (pin "1") (pinfunction "1_1") (pintype "passive"))
      (node (ref "D101") (pin "2") (pinfunction "GND_2") (pintype "power_in"))
      (node (ref "J101") (pin "A1B12") (pinfunction "GND_A1B12_A1B12") (pintype "passive"))
      (node (ref "J101") (pin "B1A12") (pinfunction "GND_B1A12_B1A12") (pintype "passive"))
      (node (ref "J106") (pin "6") (pinfunction "6_6") (pintype "passive"))
      (node (ref "R101") (pin "2") (pinfunction "2_2") (pintype "passive"))
      (node (ref "R102") (pin "2") (pinfunction "2_2") (pintype "passive"))
      (node (ref "S101") (pin "3") (pinfunction "3_3") (pintype "passive"))
      (node (ref "S102") (pin "3") (pinfunction "3_3") (pintype "passive"))
      (node (ref "S102") (pin "4") (pinfunction "4_4") (pintype "passive"))
      (node (ref "U101") (pin "1") (pinfunction "GND_1") (pintype "power_in"))
      (node (ref "U102") (pin "1") (pinfunction "GND_1") (pintype "power_in"))
      (node (ref "U103") (pin "12") (pinfunction "VSSA_12") (pintype "power_in"))
      (node (ref "U103") (pin "18") (pinfunction "VSS_18") (pintype "power_in"))
      (node (ref "U103") (pin "31") (pinfunction "VSS_31") (pintype "power_in"))
      (node (ref "U103") (pin "47") (pinfunction "VSS_47") (pintype "power_in"))
      (node (ref "U103") (pin "63") (pinfunction "VSS_63") (pintype "power_in"))
      (node (ref "X101") (pin "2") (pinfunction "2_2") (pintype "passive"))
      (node (ref "X101") (pin "4") (pinfunction "4_4") (pintype "passive"))
    )
    (net (code "59") (name "unconnected-(J101-SBU1-PadA8)") (class "Default")
      (node (ref "J101") (pin "A8") (pinfunction "SBU1_A8") (pintype "passive+no_connect"))
    )
    (net (code "60") (name "unconnected-(J101-SBU2-PadB8)") (class "Default")
      (node (ref "J101") (pin "B8") (pinfunction "SBU2_B8") (pintype "passive+no_connect"))
    )
    (net (code "61") (name "unconnected-(J101-SHIELD_1-PadS1)") (class "Default")
      (node (ref "J101") (pin "S1") (pinfunction "SHIELD_1_S1") (pintype "passive+no_connect"))
    )
    (net (code "62") (name "unconnected-(J101-SHIELD_2-PadS2)") (class "Default")
      (node (ref "J101") (pin "S2") (pinfunction "SHIELD_2_S2") (pintype "passive+no_connect"))
    )
    (net (code "63") (name "unconnected-(J101-SHIELD_3-PadS3)") (class "Default")
      (node (ref "J101") (pin "S3") (pinfunction "SHIELD_3_S3") (pintype "passive+no_connect"))
    )
    (net (code "64") (name "unconnected-(J101-SHIELD_4-PadS4)") (class "Default")
      (node (ref "J101") (pin "S4") (pinfunction "SHIELD_4_S4") (pintype "passive+no_connect"))
    )
    (net (code "65") (name "unconnected-(U103-PA10-Pad43)") (class "Default")
      (node (ref "U103") (pin "43") (pinfunction "PA10_43") (pintype "bidirectional+no_connect"))
    )
    (net (code "66") (name "unconnected-(U103-PA15(JTDI)-Pad50)") (class "Default")
      (node (ref "U103") (pin "50") (pinfunction "PA15(JTDI)_50") (pintype "bidirectional+no_connect"))
    )
    (net (code "67") (name "unconnected-(U103-PB2-Pad27)") (class "Default")
      (node (ref "U103") (pin "27") (pinfunction "PB2_27") (pintype "bidirectional+no_connect"))
    )
    (net (code "68") (name "unconnected-(U103-PB4(~{JTRST)}-Pad56)") (class "Default")
      (node (ref "U103") (pin "56") (pinfunction "PB4(~{JTRST)}_56") (pintype "bidirectional+no_connect"))
    )
    (net (code "69") (name "unconnected-(U103-PB5-Pad57)") (class "Default")
      (node (ref "U103") (pin "57") (pinfunction "PB5_57") (pintype "bidirectional+no_connect"))
    )
    (net (code "70") (name "unconnected-(U103-PB13-Pad34)") (class "Default")
      (node (ref "U103") (pin "34") (pinfunction "PB13_34") (pintype "bidirectional+no_connect"))
    )
    (net (code "71") (name "unconnected-(U103-PB15-Pad36)") (class "Default")
      (node (ref "U103") (pin "36") (pinfunction "PB15_36") (pintype "bidirectional+no_connect"))
    )
    (net (code "72") (name "unconnected-(U103-PC0-Pad8)") (class "Default")
      (node (ref "U103") (pin "8") (pinfunction "PC0_8") (pintype "bidirectional+no_connect"))
    )
    (net (code "73") (name "unconnected-(U103-PC1-Pad9)") (class "Default")
      (node (ref "U103") (pin "9") (pinfunction "PC1_9") (pintype "bidirectional+no_connect"))
    )
    (net (code "74") (name "unconnected-(U103-PC4-Pad24)") (class "Default")
      (node (ref "U103") (pin "24") (pinfunction "PC4_24") (pintype "bidirectional+no_connect"))
    )
    (net (code "75") (name "unconnected-(U103-PC12-Pad53)") (class "Default")
      (node (ref "U103") (pin "53") (pinfunction "PC12_53") (pintype "bidirectional+no_connect"))
    )
    (net (code "76") (name "unconnected-(U103-PD2-Pad54)") (class "Default")
      (node (ref "U103") (pin "54") (pinfunction "PD2_54") (pintype "bidirectional+no_connect"))
    )
  )
)
